# controller_print.net
KiCad netlist of a schematic drawn in EAGLE
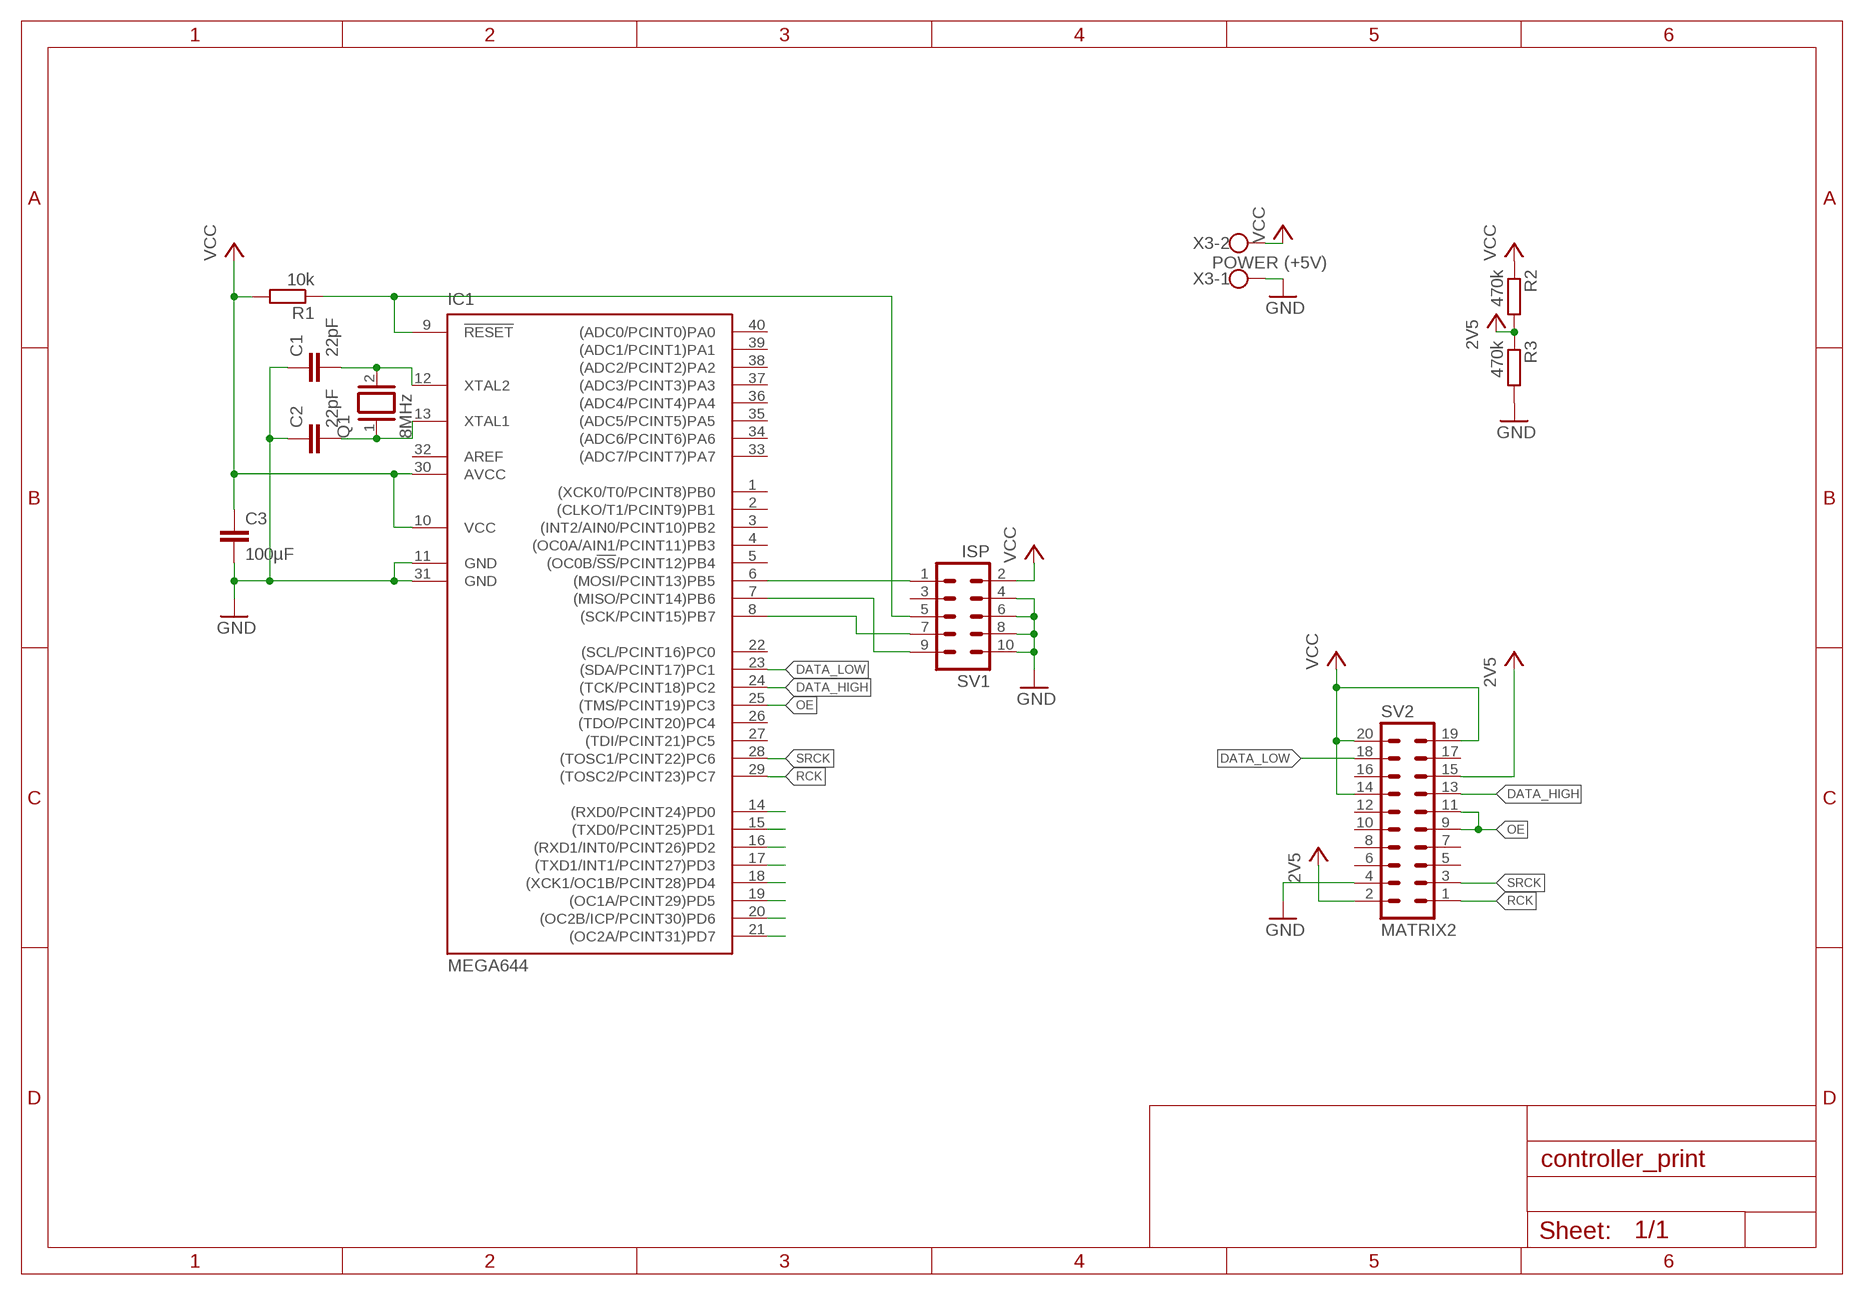
[diagram p0: schematic, sheet 1]

(export (version "E")
  (design (tool "Eeschema 10.0.6"))
  (components
    (comp (ref "C1")
      (value "22pF")
      (footprint "eagle-import:C050-024X044")
      (libsource (lib "eagle-import") (part "C-EU050-024X044"))
    )
    (comp (ref "C2")
      (value "22pF")
      (footprint "eagle-import:C050-024X044")
      (libsource (lib "eagle-import") (part "C-EU050-024X044"))
    )
    (comp (ref "C3")
      (value "100µF")
      (footprint "eagle-import:C050-030X075")
      (libsource (lib "eagle-import") (part "C-EU050-030X075"))
    )
    (comp (ref "IC1")
      (value "MEGA644")
      (footprint "eagle-import:DIL40")
      (libsource (lib "eagle-import") (part "MEGA164P/324P/644P-PU"))
    )
    (comp (ref "Q1")
      (value "8MHz")
      (footprint "eagle-import:QS")
      (libsource (lib "eagle-import") (part "XTAL/S"))
    )
    (comp (ref "R1")
      (value "10k")
      (footprint "eagle-import:0207_10")
      (libsource (lib "eagle-import") (part "R-EU_0207/10"))
    )
    (comp (ref "R2")
      (value "470k")
      (footprint "eagle-import:0207_10")
      (libsource (lib "eagle-import") (part "R-EU_0207/10"))
    )
    (comp (ref "R3")
      (value "470k")
      (footprint "eagle-import:0207_10")
      (libsource (lib "eagle-import") (part "R-EU_0207/10"))
    )
    (comp (ref "SV1")
      (value "ISP")
      (footprint "eagle-import:ML10")
      (libsource (lib "eagle-import") (part "ML10"))
    )
    (comp (ref "SV2")
      (value "MATRIX2")
      (footprint "eagle-import:ML20")
      (libsource (lib "eagle-import") (part "ML20"))
    )
    (comp (ref "X3")
      (value "POWER (+5V)")
      (footprint "eagle-import:W237-102")
      (fields (field (name "MPN") "237-102"))
      (libsource (lib "eagle-import") (part "W237-102"))
    )
  )
  (nets
    (net (code "1") (name "/AREF") (class "Default")
      (node (ref "IC1") (pin "32") (pinfunction "AREF_32") (pintype "power_in"))
    )
    (net (code "2") (name "2V5") (class "Default")
      (node (ref "R2") (pin "2") (pinfunction "2_2") (pintype "passive"))
      (node (ref "R3") (pin "1") (pinfunction "1_1") (pintype "passive"))
      (node (ref "SV2") (pin "15") (pinfunction "15_15") (pintype "passive"))
      (node (ref "SV2") (pin "2") (pinfunction "2_2") (pintype "passive"))
    )
    (net (code "3") (name "DATA_HIGH") (class "Default")
      (node (ref "IC1") (pin "24") (pinfunction "(TCK/PCINT18)PC2_24") (pintype "bidirectional"))
      (node (ref "SV2") (pin "13") (pinfunction "13_13") (pintype "passive"))
    )
    (net (code "4") (name "DATA_LOW") (class "Default")
      (node (ref "IC1") (pin "23") (pinfunction "(SDA/PCINT17)PC1_23") (pintype "bidirectional"))
      (node (ref "SV2") (pin "18") (pinfunction "18_18") (pintype "passive"))
    )
    (net (code "5") (name "GND") (class "Default")
      (node (ref "C1") (pin "1") (pinfunction "1_1") (pintype "passive"))
      (node (ref "C2") (pin "1") (pinfunction "1_1") (pintype "passive"))
      (node (ref "C3") (pin "2") (pinfunction "2_2") (pintype "passive"))
      (node (ref "IC1") (pin "11") (pinfunction "GND_11") (pintype "power_in"))
      (node (ref "IC1") (pin "31") (pinfunction "GND_31") (pintype "power_in"))
      (node (ref "R3") (pin "2") (pinfunction "2_2") (pintype "passive"))
      (node (ref "SV1") (pin "10") (pinfunction "10_10") (pintype "passive"))
      (node (ref "SV1") (pin "4") (pinfunction "4_4") (pintype "passive"))
      (node (ref "SV1") (pin "6") (pinfunction "6_6") (pintype "passive"))
      (node (ref "SV1") (pin "8") (pinfunction "8_8") (pintype "passive"))
      (node (ref "SV2") (pin "4") (pinfunction "4_4") (pintype "passive"))
      (node (ref "X3") (pin "1") (pinfunction "KL_1") (pintype "passive"))
    )
    (net (code "6") (name "Net-(IC1-(MISO{slash}PCINT14)PB6)") (class "Default")
      (node (ref "IC1") (pin "7") (pinfunction "(MISO/PCINT14)PB6_7") (pintype "bidirectional"))
      (node (ref "SV1") (pin "9") (pinfunction "9_9") (pintype "passive"))
    )
    (net (code "7") (name "Net-(IC1-(MOSI{slash}PCINT13)PB5)") (class "Default")
      (node (ref "IC1") (pin "6") (pinfunction "(MOSI/PCINT13)PB5_6") (pintype "bidirectional"))
      (node (ref "SV1") (pin "1") (pinfunction "1_1") (pintype "passive"))
    )
    (net (code "8") (name "Net-(IC1-(SCK{slash}PCINT15)PB7)") (class "Default")
      (node (ref "IC1") (pin "8") (pinfunction "(SCK/PCINT15)PB7_8") (pintype "bidirectional"))
      (node (ref "SV1") (pin "7") (pinfunction "7_7") (pintype "passive"))
    )
    (net (code "9") (name "Net-(IC1-XTAL1)") (class "Default")
      (node (ref "C2") (pin "2") (pinfunction "2_2") (pintype "passive"))
      (node (ref "IC1") (pin "13") (pinfunction "XTAL1_13") (pintype "input"))
      (node (ref "Q1") (pin "1") (pinfunction "1_1") (pintype "passive"))
    )
    (net (code "10") (name "Net-(IC1-XTAL2)") (class "Default")
      (node (ref "C1") (pin "2") (pinfunction "2_2") (pintype "passive"))
      (node (ref "IC1") (pin "12") (pinfunction "XTAL2_12") (pintype "output"))
      (node (ref "Q1") (pin "2") (pinfunction "2_2") (pintype "passive"))
    )
    (net (code "11") (name "Net-(IC1-~{RESET})") (class "Default")
      (node (ref "IC1") (pin "9") (pinfunction "~{RESET}_9") (pintype "input"))
      (node (ref "R1") (pin "1") (pinfunction "1_1") (pintype "passive"))
      (node (ref "SV1") (pin "5") (pinfunction "5_5") (pintype "passive"))
    )
    (net (code "12") (name "OE") (class "Default")
      (node (ref "IC1") (pin "25") (pinfunction "(TMS/PCINT19)PC3_25") (pintype "bidirectional"))
      (node (ref "SV2") (pin "11") (pinfunction "11_11") (pintype "passive"))
      (node (ref "SV2") (pin "9") (pinfunction "9_9") (pintype "passive"))
    )
    (net (code "13") (name "RCK") (class "Default")
      (node (ref "IC1") (pin "29") (pinfunction "(TOSC2/PCINT23)PC7_29") (pintype "bidirectional"))
      (node (ref "SV2") (pin "1") (pinfunction "1_1") (pintype "passive"))
    )
    (net (code "14") (name "SRCK") (class "Default")
      (node (ref "IC1") (pin "28") (pinfunction "(TOSC1/PCINT22)PC6_28") (pintype "bidirectional"))
      (node (ref "SV2") (pin "3") (pinfunction "3_3") (pintype "passive"))
    )
    (net (code "15") (name "VCC") (class "Default")
      (node (ref "C3") (pin "1") (pinfunction "1_1") (pintype "passive"))
      (node (ref "IC1") (pin "10") (pinfunction "VCC_10") (pintype "power_in"))
      (node (ref "IC1") (pin "30") (pinfunction "AVCC_30") (pintype "power_in"))
      (node (ref "R1") (pin "2") (pinfunction "2_2") (pintype "passive"))
      (node (ref "R2") (pin "1") (pinfunction "1_1") (pintype "passive"))
      (node (ref "SV1") (pin "2") (pinfunction "2_2") (pintype "passive"))
      (node (ref "SV2") (pin "14") (pinfunction "14_14") (pintype "passive"))
      (node (ref "SV2") (pin "19") (pinfunction "19_19") (pintype "passive"))
      (node (ref "SV2") (pin "20") (pinfunction "20_20") (pintype "passive"))
      (node (ref "X3") (pin "2") (pinfunction "KL_2") (pintype "passive"))
    )
    (net (code "16") (name "unconnected-(IC1-(ADC0{slash}PCINT0)PA0-Pad40)") (class "Default")
      (node (ref "IC1") (pin "40") (pinfunction "(ADC0/PCINT0)PA0_40") (pintype "bidirectional"))
    )
    (net (code "17") (name "unconnected-(IC1-(ADC1{slash}PCINT1)PA1-Pad39)") (class "Default")
      (node (ref "IC1") (pin "39") (pinfunction "(ADC1/PCINT1)PA1_39") (pintype "bidirectional"))
    )
    (net (code "18") (name "unconnected-(IC1-(ADC2{slash}PCINT2)PA2-Pad38)") (class "Default")
      (node (ref "IC1") (pin "38") (pinfunction "(ADC2/PCINT2)PA2_38") (pintype "bidirectional"))
    )
    (net (code "19") (name "unconnected-(IC1-(ADC3{slash}PCINT3)PA3-Pad37)") (class "Default")
      (node (ref "IC1") (pin "37") (pinfunction "(ADC3/PCINT3)PA3_37") (pintype "bidirectional"))
    )
    (net (code "20") (name "unconnected-(IC1-(ADC4{slash}PCINT4)PA4-Pad36)") (class "Default")
      (node (ref "IC1") (pin "36") (pinfunction "(ADC4/PCINT4)PA4_36") (pintype "bidirectional"))
    )
    (net (code "21") (name "unconnected-(IC1-(ADC5{slash}PCINT5)PA5-Pad35)") (class "Default")
      (node (ref "IC1") (pin "35") (pinfunction "(ADC5/PCINT5)PA5_35") (pintype "bidirectional"))
    )
    (net (code "22") (name "unconnected-(IC1-(ADC6{slash}PCINT6)PA6-Pad34)") (class "Default")
      (node (ref "IC1") (pin "34") (pinfunction "(ADC6/PCINT6)PA6_34") (pintype "bidirectional"))
    )
    (net (code "23") (name "unconnected-(IC1-(ADC7{slash}PCINT7)PA7-Pad33)") (class "Default")
      (node (ref "IC1") (pin "33") (pinfunction "(ADC7/PCINT7)PA7_33") (pintype "bidirectional"))
    )
    (net (code "24") (name "unconnected-(IC1-(CLKO{slash}T1{slash}PCINT9)PB1-Pad2)") (class "Default")
      (node (ref "IC1") (pin "2") (pinfunction "(CLKO/T1/PCINT9)PB1_2") (pintype "bidirectional"))
    )
    (net (code "25") (name "unconnected-(IC1-(INT2{slash}AIN0{slash}PCINT10)PB2-Pad3)") (class "Default")
      (node (ref "IC1") (pin "3") (pinfunction "(INT2/AIN0/PCINT10)PB2_3") (pintype "bidirectional"))
    )
    (net (code "26") (name "unconnected-(IC1-(OC0A{slash}AIN1{slash}PCINT11)PB3-Pad4)") (class "Default")
      (node (ref "IC1") (pin "4") (pinfunction "(OC0A/AIN1/PCINT11)PB3_4") (pintype "bidirectional"))
    )
    (net (code "27") (name "unconnected-(IC1-(OC0B{slash}~{SS}{slash}PCINT12)PB4-Pad5)") (class "Default")
      (node (ref "IC1") (pin "5") (pinfunction "(OC0B/~{SS}/PCINT12)PB4_5") (pintype "bidirectional"))
    )
    (net (code "28") (name "unconnected-(IC1-(OC1A{slash}PCINT29)PD5-Pad19)") (class "Default")
      (node (ref "IC1") (pin "19") (pinfunction "(OC1A/PCINT29)PD5_19") (pintype "bidirectional"))
    )
    (net (code "29") (name "unconnected-(IC1-(OC2A{slash}PCINT31)PD7-Pad21)") (class "Default")
      (node (ref "IC1") (pin "21") (pinfunction "(OC2A/PCINT31)PD7_21") (pintype "bidirectional"))
    )
    (net (code "30") (name "unconnected-(IC1-(OC2B{slash}ICP{slash}PCINT30)PD6-Pad20)") (class "Default")
      (node (ref "IC1") (pin "20") (pinfunction "(OC2B/ICP/PCINT30)PD6_20") (pintype "bidirectional"))
    )
    (net (code "31") (name "unconnected-(IC1-(RXD0{slash}PCINT24)PD0-Pad14)") (class "Default")
      (node (ref "IC1") (pin "14") (pinfunction "(RXD0/PCINT24)PD0_14") (pintype "bidirectional"))
    )
    (net (code "32") (name "unconnected-(IC1-(RXD1{slash}INT0{slash}PCINT26)PD2-Pad16)") (class "Default")
      (node (ref "IC1") (pin "16") (pinfunction "(RXD1/INT0/PCINT26)PD2_16") (pintype "bidirectional"))
    )
    (net (code "33") (name "unconnected-(IC1-(SCL{slash}PCINT16)PC0-Pad22)") (class "Default")
      (node (ref "IC1") (pin "22") (pinfunction "(SCL/PCINT16)PC0_22") (pintype "bidirectional"))
    )
    (net (code "34") (name "unconnected-(IC1-(TDI{slash}PCINT21)PC5-Pad27)") (class "Default")
      (node (ref "IC1") (pin "27") (pinfunction "(TDI/PCINT21)PC5_27") (pintype "bidirectional"))
    )
    (net (code "35") (name "unconnected-(IC1-(TDO{slash}PCINT20)PC4-Pad26)") (class "Default")
      (node (ref "IC1") (pin "26") (pinfunction "(TDO/PCINT20)PC4_26") (pintype "bidirectional"))
    )
    (net (code "36") (name "unconnected-(IC1-(TXD0{slash}PCINT25)PD1-Pad15)") (class "Default")
      (node (ref "IC1") (pin "15") (pinfunction "(TXD0/PCINT25)PD1_15") (pintype "bidirectional"))
    )
    (net (code "37") (name "unconnected-(IC1-(TXD1{slash}INT1{slash}PCINT27)PD3-Pad17)") (class "Default")
      (node (ref "IC1") (pin "17") (pinfunction "(TXD1/INT1/PCINT27)PD3_17") (pintype "bidirectional"))
    )
    (net (code "38") (name "unconnected-(IC1-(XCK0{slash}T0{slash}PCINT8)PB0-Pad1)") (class "Default")
      (node (ref "IC1") (pin "1") (pinfunction "(XCK0/T0/PCINT8)PB0_1") (pintype "bidirectional"))
    )
    (net (code "39") (name "unconnected-(IC1-(XCK1{slash}OC1B{slash}PCINT28)PD4-Pad18)") (class "Default")
      (node (ref "IC1") (pin "18") (pinfunction "(XCK1/OC1B/PCINT28)PD4_18") (pintype "bidirectional"))
    )
    (net (code "40") (name "unconnected-(SV1-Pad3)") (class "Default")
      (node (ref "SV1") (pin "3") (pinfunction "3_3") (pintype "passive"))
    )
    (net (code "41") (name "unconnected-(SV2-Pad5)") (class "Default")
      (node (ref "SV2") (pin "5") (pinfunction "5_5") (pintype "passive"))
    )
    (net (code "42") (name "unconnected-(SV2-Pad6)") (class "Default")
      (node (ref "SV2") (pin "6") (pinfunction "6_6") (pintype "passive"))
    )
    (net (code "43") (name "unconnected-(SV2-Pad7)") (class "Default")
      (node (ref "SV2") (pin "7") (pinfunction "7_7") (pintype "passive"))
    )
    (net (code "44") (name "unconnected-(SV2-Pad8)") (class "Default")
      (node (ref "SV2") (pin "8") (pinfunction "8_8") (pintype "passive"))
    )
    (net (code "45") (name "unconnected-(SV2-Pad10)") (class "Default")
      (node (ref "SV2") (pin "10") (pinfunction "10_10") (pintype "passive"))
    )
    (net (code "46") (name "unconnected-(SV2-Pad12)") (class "Default")
      (node (ref "SV2") (pin "12") (pinfunction "12_12") (pintype "passive"))
    )
    (net (code "47") (name "unconnected-(SV2-Pad16)") (class "Default")
      (node (ref "SV2") (pin "16") (pinfunction "16_16") (pintype "passive"))
    )
    (net (code "48") (name "unconnected-(SV2-Pad17)") (class "Default")
      (node (ref "SV2") (pin "17") (pinfunction "17_17") (pintype "passive"))
    )
  )
)
